# POWER.net
KiCad netlist of a schematic drawn in Altium Designer
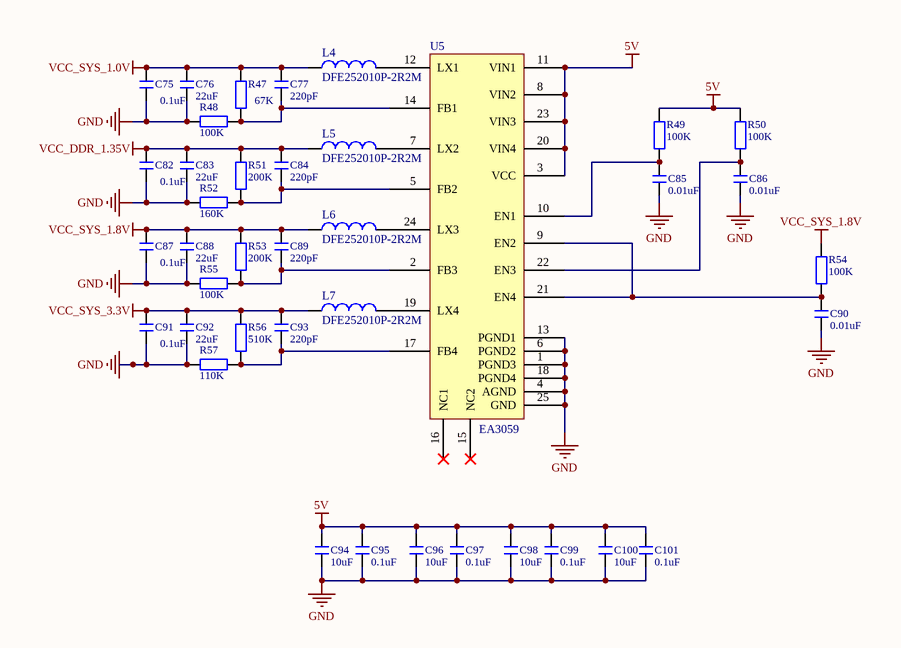
[diagram p0: POWER.SchDoc]

(export (version "E")
  (design (tool "Eeschema 10.0.6"))
  (components
    (comp (ref "C75")
      (value "0.1uF")
      (footprint "C 0402")
      (description "无极性贴片电容")
      (fields (field (name "版权归属") "正点原子"))
      (libsource (lib "20240511") (part "C"))
    )
    (comp (ref "C76")
      (value "22uF")
      (footprint "C 0603")
      (description "无极性贴片电容")
      (fields (field (name "版权归属") "正点原子"))
      (libsource (lib "20240511") (part "C"))
    )
    (comp (ref "C77")
      (value "220pF")
      (footprint "C 0402")
      (description "无极性贴片电容")
      (fields (field (name "版权归属") "正点原子"))
      (libsource (lib "20240511") (part "C"))
    )
    (comp (ref "C82")
      (value "0.1uF")
      (footprint "C 0402")
      (description "无极性贴片电容")
      (fields (field (name "版权归属") "正点原子"))
      (libsource (lib "20240511") (part "C"))
    )
    (comp (ref "C83")
      (value "22uF")
      (footprint "C 0603")
      (description "无极性贴片电容")
      (fields (field (name "版权归属") "正点原子"))
      (libsource (lib "20240511") (part "C"))
    )
    (comp (ref "C84")
      (value "220pF")
      (footprint "C 0402")
      (description "无极性贴片电容")
      (fields (field (name "版权归属") "正点原子"))
      (libsource (lib "20240511") (part "C"))
    )
    (comp (ref "C85")
      (value "0.01uF")
      (footprint "C 0402")
      (description "无极性贴片电容")
      (fields (field (name "版权归属") "正点原子"))
      (libsource (lib "20240511") (part "C"))
    )
    (comp (ref "C86")
      (value "0.01uF")
      (footprint "C 0402")
      (description "无极性贴片电容")
      (fields (field (name "版权归属") "正点原子"))
      (libsource (lib "20240511") (part "C"))
    )
    (comp (ref "C87")
      (value "0.1uF")
      (footprint "C 0402")
      (description "无极性贴片电容")
      (fields (field (name "版权归属") "正点原子"))
      (libsource (lib "20240511") (part "C"))
    )
    (comp (ref "C88")
      (value "22uF")
      (footprint "C 0603")
      (description "无极性贴片电容")
      (fields (field (name "版权归属") "正点原子"))
      (libsource (lib "20240511") (part "C"))
    )
    (comp (ref "C89")
      (value "220pF")
      (footprint "C 0402")
      (description "无极性贴片电容")
      (fields (field (name "版权归属") "正点原子"))
      (libsource (lib "20240511") (part "C"))
    )
    (comp (ref "C90")
      (value "0.01uF")
      (footprint "C 0402")
      (description "无极性贴片电容")
      (fields (field (name "版权归属") "正点原子"))
      (libsource (lib "20240511") (part "C"))
    )
    (comp (ref "C91")
      (value "0.1uF")
      (footprint "C 0402")
      (description "无极性贴片电容")
      (fields (field (name "版权归属") "正点原子"))
      (libsource (lib "20240511") (part "C"))
    )
    (comp (ref "C92")
      (value "22uF")
      (footprint "C 0603")
      (description "无极性贴片电容")
      (fields (field (name "版权归属") "正点原子"))
      (libsource (lib "20240511") (part "C"))
    )
    (comp (ref "C93")
      (value "220pF")
      (footprint "C 0402")
      (description "无极性贴片电容")
      (fields (field (name "版权归属") "正点原子"))
      (libsource (lib "20240511") (part "C"))
    )
    (comp (ref "C94")
      (value "10uF")
      (footprint "C 0603")
      (description "无极性贴片电容")
      (fields (field (name "版权归属") "正点原子"))
      (libsource (lib "20240511") (part "C"))
    )
    (comp (ref "C95")
      (value "0.1uF")
      (footprint "C 0402")
      (description "无极性贴片电容")
      (fields (field (name "版权归属") "正点原子"))
      (libsource (lib "20240511") (part "C"))
    )
    (comp (ref "C96")
      (value "10uF")
      (footprint "C 0603")
      (description "无极性贴片电容")
      (fields (field (name "版权归属") "正点原子"))
      (libsource (lib "20240511") (part "C"))
    )
    (comp (ref "C97")
      (value "0.1uF")
      (footprint "C 0402")
      (description "无极性贴片电容")
      (fields (field (name "版权归属") "正点原子"))
      (libsource (lib "20240511") (part "C"))
    )
    (comp (ref "C98")
      (value "10uF")
      (footprint "C 0603")
      (description "无极性贴片电容")
      (fields (field (name "版权归属") "正点原子"))
      (libsource (lib "20240511") (part "C"))
    )
    (comp (ref "C99")
      (value "0.1uF")
      (footprint "C 0402")
      (description "无极性贴片电容")
      (fields (field (name "版权归属") "正点原子"))
      (libsource (lib "20240511") (part "C"))
    )
    (comp (ref "C100")
      (value "10uF")
      (footprint "C 0603")
      (description "无极性贴片电容")
      (fields (field (name "版权归属") "正点原子"))
      (libsource (lib "20240511") (part "C"))
    )
    (comp (ref "C101")
      (value "0.1uF")
      (footprint "C 0402")
      (description "无极性贴片电容")
      (fields (field (name "版权归属") "正点原子"))
      (libsource (lib "20240511") (part "C"))
    )
    (comp (ref "L4")
      (value "DFE252010P-2R2M")
      (footprint "L2520")
      (description "电感")
      (libsource (lib "20240511") (part "DFE252010P-2R2M"))
    )
    (comp (ref "L5")
      (value "DFE252010P-2R2M")
      (footprint "L2520")
      (description "电感")
      (libsource (lib "20240511") (part "DFE252010P-2R2M"))
    )
    (comp (ref "L6")
      (value "DFE252010P-2R2M")
      (footprint "L2520")
      (description "电感")
      (libsource (lib "20240511") (part "DFE252010P-2R2M"))
    )
    (comp (ref "L7")
      (value "DFE252010P-2R2M")
      (footprint "L2520")
      (description "电感")
      (libsource (lib "20240511") (part "DFE252010P-2R2M"))
    )
    (comp (ref "R47")
      (value "67K")
      (footprint "R 0402")
      (description "贴片电阻")
      (fields (field (name "版权归属") "正点原子"))
      (libsource (lib "20240511") (part "R"))
    )
    (comp (ref "R48")
      (value "100K")
      (footprint "R 0402")
      (description "贴片电阻")
      (fields (field (name "版权归属") "正点原子"))
      (libsource (lib "20240511") (part "R"))
    )
    (comp (ref "R49")
      (value "100K")
      (footprint "R 0402")
      (description "贴片电阻")
      (fields (field (name "版权归属") "正点原子"))
      (libsource (lib "20240511") (part "R"))
    )
    (comp (ref "R50")
      (value "100K")
      (footprint "R 0402")
      (description "贴片电阻")
      (fields (field (name "版权归属") "正点原子"))
      (libsource (lib "20240511") (part "R"))
    )
    (comp (ref "R51")
      (value "200K")
      (footprint "R 0402")
      (description "贴片电阻")
      (fields (field (name "版权归属") "正点原子"))
      (libsource (lib "20240511") (part "R"))
    )
    (comp (ref "R52")
      (value "160K")
      (footprint "R 0402")
      (description "贴片电阻")
      (fields (field (name "版权归属") "正点原子"))
      (libsource (lib "20240511") (part "R"))
    )
    (comp (ref "R53")
      (value "200K")
      (footprint "R 0402")
      (description "贴片电阻")
      (fields (field (name "版权归属") "正点原子"))
      (libsource (lib "20240511") (part "R"))
    )
    (comp (ref "R54")
      (value "100K")
      (footprint "R 0402")
      (description "贴片电阻")
      (fields (field (name "版权归属") "正点原子"))
      (libsource (lib "20240511") (part "R"))
    )
    (comp (ref "R55")
      (value "100K")
      (footprint "R 0402")
      (description "贴片电阻")
      (fields (field (name "版权归属") "正点原子"))
      (libsource (lib "20240511") (part "R"))
    )
    (comp (ref "R56")
      (value "510K")
      (footprint "R 0402")
      (description "贴片电阻")
      (fields (field (name "版权归属") "正点原子"))
      (libsource (lib "20240511") (part "R"))
    )
    (comp (ref "R57")
      (value "110K")
      (footprint "R 0402")
      (description "贴片电阻")
      (fields (field (name "版权归属") "正点原子"))
      (libsource (lib "20240511") (part "R"))
    )
    (comp (ref "U5")
      (value "EA3059")
      (footprint "VQFN-24_L4.0-W4.0-P0.50-TL-EP2.5")
      (description "四路电源管理")
      (libsource (lib "20240511") (part "EA3059"))
    )
  )
  (nets
    (net (code "1") (name "5V") (class "Default")
      (node (ref "C100") (pin "1") (pinfunction "1_1") (pintype "passive"))
      (node (ref "C101") (pin "1") (pinfunction "1_1") (pintype "passive"))
      (node (ref "C94") (pin "1") (pinfunction "1_1") (pintype "passive"))
      (node (ref "C95") (pin "1") (pinfunction "1_1") (pintype "passive"))
      (node (ref "C96") (pin "1") (pinfunction "1_1") (pintype "passive"))
      (node (ref "C97") (pin "1") (pinfunction "1_1") (pintype "passive"))
      (node (ref "C98") (pin "1") (pinfunction "1_1") (pintype "passive"))
      (node (ref "C99") (pin "1") (pinfunction "1_1") (pintype "passive"))
      (node (ref "R49") (pin "2") (pinfunction "2_2") (pintype "passive"))
      (node (ref "R50") (pin "2") (pinfunction "2_2") (pintype "passive"))
      (node (ref "U5") (pin "11") (pinfunction "VIN1_11") (pintype "passive"))
      (node (ref "U5") (pin "20") (pinfunction "VIN4_20") (pintype "passive"))
      (node (ref "U5") (pin "23") (pinfunction "VIN3_23") (pintype "passive"))
      (node (ref "U5") (pin "3") (pinfunction "VCC_3") (pintype "passive"))
      (node (ref "U5") (pin "8") (pinfunction "VIN2_8") (pintype "passive"))
    )
    (net (code "2") (name "GND") (class "Default")
      (node (ref "C100") (pin "2") (pinfunction "2_2") (pintype "passive"))
      (node (ref "C101") (pin "2") (pinfunction "2_2") (pintype "passive"))
      (node (ref "C75") (pin "1") (pinfunction "1_1") (pintype "passive"))
      (node (ref "C76") (pin "1") (pinfunction "1_1") (pintype "passive"))
      (node (ref "C82") (pin "1") (pinfunction "1_1") (pintype "passive"))
      (node (ref "C83") (pin "1") (pinfunction "1_1") (pintype "passive"))
      (node (ref "C85") (pin "1") (pinfunction "1_1") (pintype "passive"))
      (node (ref "C86") (pin "2") (pinfunction "2_2") (pintype "passive"))
      (node (ref "C87") (pin "1") (pinfunction "1_1") (pintype "passive"))
      (node (ref "C88") (pin "1") (pinfunction "1_1") (pintype "passive"))
      (node (ref "C90") (pin "2") (pinfunction "2_2") (pintype "passive"))
      (node (ref "C91") (pin "1") (pinfunction "1_1") (pintype "passive"))
      (node (ref "C92") (pin "1") (pinfunction "1_1") (pintype "passive"))
      (node (ref "C94") (pin "2") (pinfunction "2_2") (pintype "passive"))
      (node (ref "C95") (pin "2") (pinfunction "2_2") (pintype "passive"))
      (node (ref "C96") (pin "2") (pinfunction "2_2") (pintype "passive"))
      (node (ref "C97") (pin "2") (pinfunction "2_2") (pintype "passive"))
      (node (ref "C98") (pin "2") (pinfunction "2_2") (pintype "passive"))
      (node (ref "C99") (pin "2") (pinfunction "2_2") (pintype "passive"))
      (node (ref "R48") (pin "2") (pinfunction "2_2") (pintype "passive"))
      (node (ref "R52") (pin "2") (pinfunction "2_2") (pintype "passive"))
      (node (ref "R55") (pin "2") (pinfunction "2_2") (pintype "passive"))
      (node (ref "R57") (pin "2") (pinfunction "2_2") (pintype "passive"))
      (node (ref "U5") (pin "1") (pinfunction "PGND3_1") (pintype "passive"))
      (node (ref "U5") (pin "13") (pinfunction "PGND1_13") (pintype "passive"))
      (node (ref "U5") (pin "18") (pinfunction "PGND4_18") (pintype "passive"))
      (node (ref "U5") (pin "25") (pinfunction "GND_25") (pintype "passive"))
      (node (ref "U5") (pin "4") (pinfunction "AGND_4") (pintype "passive"))
      (node (ref "U5") (pin "6") (pinfunction "PGND2_6") (pintype "passive"))
    )
    (net (code "3") (name "Net-(L4-102)") (class "Default")
      (node (ref "L4") (pin "2") (pinfunction "102_2") (pintype "passive"))
      (node (ref "U5") (pin "12") (pinfunction "LX1_12") (pintype "passive"))
    )
    (net (code "4") (name "Net-(L5-102)") (class "Default")
      (node (ref "L5") (pin "2") (pinfunction "102_2") (pintype "passive"))
      (node (ref "U5") (pin "7") (pinfunction "LX2_7") (pintype "passive"))
    )
    (net (code "5") (name "Net-(L6-102)") (class "Default")
      (node (ref "L6") (pin "2") (pinfunction "102_2") (pintype "passive"))
      (node (ref "U5") (pin "24") (pinfunction "LX3_24") (pintype "passive"))
    )
    (net (code "6") (name "Net-(L7-102)") (class "Default")
      (node (ref "L7") (pin "2") (pinfunction "102_2") (pintype "passive"))
      (node (ref "U5") (pin "19") (pinfunction "LX4_19") (pintype "passive"))
    )
    (net (code "7") (name "Net-(U5-EN1)") (class "Default")
      (node (ref "C85") (pin "2") (pinfunction "2_2") (pintype "passive"))
      (node (ref "R49") (pin "1") (pinfunction "1_1") (pintype "passive"))
      (node (ref "U5") (pin "10") (pinfunction "EN1_10") (pintype "passive"))
    )
    (net (code "8") (name "Net-(U5-EN2)") (class "Default")
      (node (ref "C90") (pin "1") (pinfunction "1_1") (pintype "passive"))
      (node (ref "R54") (pin "1") (pinfunction "1_1") (pintype "passive"))
      (node (ref "U5") (pin "21") (pinfunction "EN4_21") (pintype "passive"))
      (node (ref "U5") (pin "9") (pinfunction "EN2_9") (pintype "passive"))
    )
    (net (code "9") (name "Net-(U5-EN3)") (class "Default")
      (node (ref "C86") (pin "1") (pinfunction "1_1") (pintype "passive"))
      (node (ref "R50") (pin "1") (pinfunction "1_1") (pintype "passive"))
      (node (ref "U5") (pin "22") (pinfunction "EN3_22") (pintype "passive"))
    )
    (net (code "10") (name "Net-(U5-FB1)") (class "Default")
      (node (ref "C77") (pin "1") (pinfunction "1_1") (pintype "passive"))
      (node (ref "R47") (pin "1") (pinfunction "1_1") (pintype "passive"))
      (node (ref "R48") (pin "1") (pinfunction "1_1") (pintype "passive"))
      (node (ref "U5") (pin "14") (pinfunction "FB1_14") (pintype "passive"))
    )
    (net (code "11") (name "Net-(U5-FB2)") (class "Default")
      (node (ref "C84") (pin "1") (pinfunction "1_1") (pintype "passive"))
      (node (ref "R51") (pin "1") (pinfunction "1_1") (pintype "passive"))
      (node (ref "R52") (pin "1") (pinfunction "1_1") (pintype "passive"))
      (node (ref "U5") (pin "5") (pinfunction "FB2_5") (pintype "passive"))
    )
    (net (code "12") (name "Net-(U5-FB3)") (class "Default")
      (node (ref "C89") (pin "1") (pinfunction "1_1") (pintype "passive"))
      (node (ref "R53") (pin "1") (pinfunction "1_1") (pintype "passive"))
      (node (ref "R55") (pin "1") (pinfunction "1_1") (pintype "passive"))
      (node (ref "U5") (pin "2") (pinfunction "FB3_2") (pintype "passive"))
    )
    (net (code "13") (name "Net-(U5-FB4)") (class "Default")
      (node (ref "C93") (pin "1") (pinfunction "1_1") (pintype "passive"))
      (node (ref "R56") (pin "1") (pinfunction "1_1") (pintype "passive"))
      (node (ref "R57") (pin "1") (pinfunction "1_1") (pintype "passive"))
      (node (ref "U5") (pin "17") (pinfunction "FB4_17") (pintype "passive"))
    )
    (net (code "14") (name "VCC_DDR_1.35V") (class "Default")
      (node (ref "C82") (pin "2") (pinfunction "2_2") (pintype "passive"))
      (node (ref "C83") (pin "2") (pinfunction "2_2") (pintype "passive"))
      (node (ref "C84") (pin "2") (pinfunction "2_2") (pintype "passive"))
      (node (ref "L5") (pin "1") (pinfunction "1_1") (pintype "passive"))
      (node (ref "R51") (pin "2") (pinfunction "2_2") (pintype "passive"))
    )
    (net (code "15") (name "VCC_SYS_1.0V") (class "Default")
      (node (ref "C75") (pin "2") (pinfunction "2_2") (pintype "passive"))
      (node (ref "C76") (pin "2") (pinfunction "2_2") (pintype "passive"))
      (node (ref "C77") (pin "2") (pinfunction "2_2") (pintype "passive"))
      (node (ref "L4") (pin "1") (pinfunction "1_1") (pintype "passive"))
      (node (ref "R47") (pin "2") (pinfunction "2_2") (pintype "passive"))
    )
    (net (code "16") (name "VCC_SYS_1.8V") (class "Default")
      (node (ref "C87") (pin "2") (pinfunction "2_2") (pintype "passive"))
      (node (ref "C88") (pin "2") (pinfunction "2_2") (pintype "passive"))
      (node (ref "C89") (pin "2") (pinfunction "2_2") (pintype "passive"))
      (node (ref "L6") (pin "1") (pinfunction "1_1") (pintype "passive"))
      (node (ref "R53") (pin "2") (pinfunction "2_2") (pintype "passive"))
      (node (ref "R54") (pin "2") (pinfunction "2_2") (pintype "passive"))
    )
    (net (code "17") (name "VCC_SYS_3.3V") (class "Default")
      (node (ref "C91") (pin "2") (pinfunction "2_2") (pintype "passive"))
      (node (ref "C92") (pin "2") (pinfunction "2_2") (pintype "passive"))
      (node (ref "C93") (pin "2") (pinfunction "2_2") (pintype "passive"))
      (node (ref "L7") (pin "1") (pinfunction "1_1") (pintype "passive"))
      (node (ref "R56") (pin "2") (pinfunction "2_2") (pintype "passive"))
    )
    (net (code "18") (name "unconnected-(U5-NC1-Pad16)") (class "Default")
      (node (ref "U5") (pin "16") (pinfunction "NC1_16") (pintype "passive+no_connect"))
    )
    (net (code "19") (name "unconnected-(U5-NC2-Pad15)") (class "Default")
      (node (ref "U5") (pin "15") (pinfunction "NC2_15") (pintype "passive+no_connect"))
    )
  )
)
